# Front_LEDs_v1b.net
KiCad netlist of a schematic drawn in EAGLE
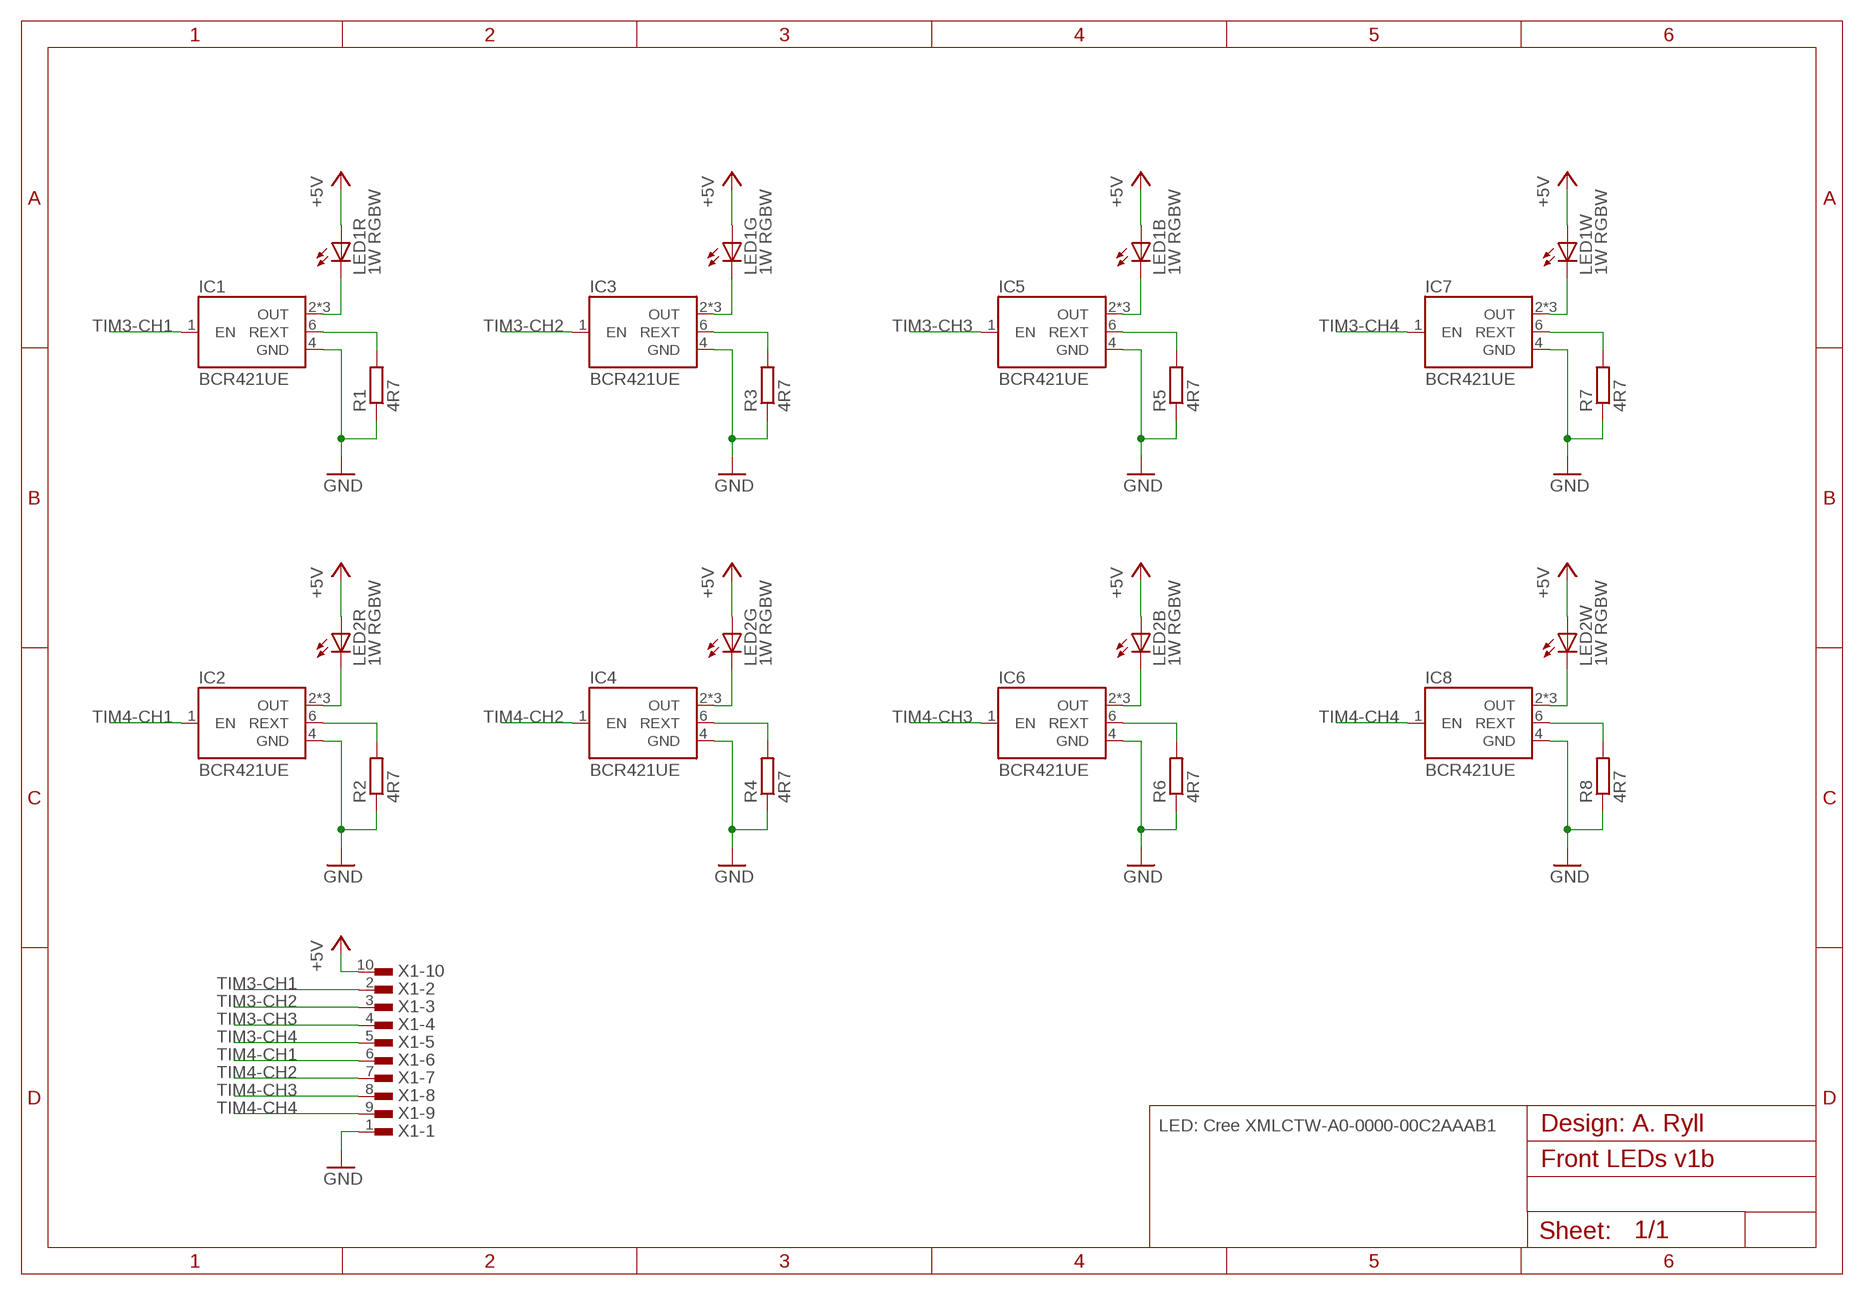
[diagram p0: schematic, sheet 1]

(export (version "E")
  (design (tool "Eeschema 10.0.6"))
  (components
    (comp (ref "IC1")
      (value "BCR421UE")
      (footprint "eagle-import:SOT26")
      (libsource (lib "eagle-import") (part "BCR420_1"))
    )
    (comp (ref "IC2")
      (value "BCR421UE")
      (footprint "eagle-import:SOT26")
      (libsource (lib "eagle-import") (part "BCR420_1"))
    )
    (comp (ref "IC3")
      (value "BCR421UE")
      (footprint "eagle-import:SOT26")
      (libsource (lib "eagle-import") (part "BCR420_1"))
    )
    (comp (ref "IC4")
      (value "BCR421UE")
      (footprint "eagle-import:SOT26")
      (libsource (lib "eagle-import") (part "BCR420_1"))
    )
    (comp (ref "IC5")
      (value "BCR421UE")
      (footprint "eagle-import:SOT26")
      (libsource (lib "eagle-import") (part "BCR420_1"))
    )
    (comp (ref "IC6")
      (value "BCR421UE")
      (footprint "eagle-import:SOT26")
      (libsource (lib "eagle-import") (part "BCR420_1"))
    )
    (comp (ref "IC7")
      (value "BCR421UE")
      (footprint "eagle-import:SOT26")
      (libsource (lib "eagle-import") (part "BCR420_1"))
    )
    (comp (ref "IC8")
      (value "BCR421UE")
      (footprint "eagle-import:SOT26")
      (libsource (lib "eagle-import") (part "BCR420_1"))
    )
    (comp (ref "LED1")
      (value "1W RGBW")
      (footprint "eagle-import:CREE-XLAMP")
      (fields (field (name "PARTNR") "XMLCTW-A0-0000-00C2AAAB1"))
      (libsource (lib "eagle-import") (part "CREE-XLAMP"))
    )
    (comp (ref "LED2")
      (value "1W RGBW")
      (footprint "eagle-import:CREE-XLAMP")
      (fields (field (name "PARTNR") "XMLCTW-A0-0000-00C2AAAB1"))
      (libsource (lib "eagle-import") (part "CREE-XLAMP"))
    )
    (comp (ref "R1")
      (value "4R7")
      (footprint "eagle-import:R0805")
      (libsource (lib "eagle-import") (part "R-EU_R0805"))
    )
    (comp (ref "R2")
      (value "4R7")
      (footprint "eagle-import:R0805")
      (libsource (lib "eagle-import") (part "R-EU_R0805"))
    )
    (comp (ref "R3")
      (value "4R7")
      (footprint "eagle-import:R0805")
      (libsource (lib "eagle-import") (part "R-EU_R0805"))
    )
    (comp (ref "R4")
      (value "4R7")
      (footprint "eagle-import:R0805")
      (libsource (lib "eagle-import") (part "R-EU_R0805"))
    )
    (comp (ref "R5")
      (value "4R7")
      (footprint "eagle-import:R0805")
      (libsource (lib "eagle-import") (part "R-EU_R0805"))
    )
    (comp (ref "R6")
      (value "4R7")
      (footprint "eagle-import:R0805")
      (libsource (lib "eagle-import") (part "R-EU_R0805"))
    )
    (comp (ref "R7")
      (value "4R7")
      (footprint "eagle-import:R0805")
      (libsource (lib "eagle-import") (part "R-EU_R0805"))
    )
    (comp (ref "R8")
      (value "4R7")
      (footprint "eagle-import:R0805")
      (libsource (lib "eagle-import") (part "R-EU_R0805"))
    )
    (comp (ref "X1")
      (value "TE-FPC-1MM-10H")
      (footprint "eagle-import:TE-1-84952-0")
      (libsource (lib "eagle-import") (part "TE-FPC-1MM-10H"))
    )
  )
  (nets
    (net (code "1") (name "+5V") (class "Default")
      (node (ref "LED1") (pin "1") (pinfunction "A_1") (pintype "passive"))
      (node (ref "LED1") (pin "2") (pinfunction "A_2") (pintype "passive"))
      (node (ref "LED1") (pin "3") (pinfunction "A_3") (pintype "passive"))
      (node (ref "LED1") (pin "4") (pinfunction "A_4") (pintype "passive"))
      (node (ref "LED2") (pin "1") (pinfunction "A_1") (pintype "passive"))
      (node (ref "LED2") (pin "2") (pinfunction "A_2") (pintype "passive"))
      (node (ref "LED2") (pin "3") (pinfunction "A_3") (pintype "passive"))
      (node (ref "LED2") (pin "4") (pinfunction "A_4") (pintype "passive"))
      (node (ref "X1") (pin "10") (pinfunction "-1_10") (pintype "bidirectional"))
    )
    (net (code "2") (name "/TIM3-CH1") (class "Default")
      (node (ref "IC1") (pin "1") (pinfunction "EN_1") (pintype "bidirectional"))
      (node (ref "X1") (pin "2") (pinfunction "-1_2") (pintype "bidirectional"))
    )
    (net (code "3") (name "/TIM3-CH2") (class "Default")
      (node (ref "IC3") (pin "1") (pinfunction "EN_1") (pintype "bidirectional"))
      (node (ref "X1") (pin "3") (pinfunction "-1_3") (pintype "bidirectional"))
    )
    (net (code "4") (name "/TIM3-CH3") (class "Default")
      (node (ref "IC5") (pin "1") (pinfunction "EN_1") (pintype "bidirectional"))
      (node (ref "X1") (pin "4") (pinfunction "-1_4") (pintype "bidirectional"))
    )
    (net (code "5") (name "/TIM3-CH4") (class "Default")
      (node (ref "IC7") (pin "1") (pinfunction "EN_1") (pintype "bidirectional"))
      (node (ref "X1") (pin "5") (pinfunction "-1_5") (pintype "bidirectional"))
    )
    (net (code "6") (name "/TIM4-CH1") (class "Default")
      (node (ref "IC2") (pin "1") (pinfunction "EN_1") (pintype "bidirectional"))
      (node (ref "X1") (pin "6") (pinfunction "-1_6") (pintype "bidirectional"))
    )
    (net (code "7") (name "/TIM4-CH2") (class "Default")
      (node (ref "IC4") (pin "1") (pinfunction "EN_1") (pintype "bidirectional"))
      (node (ref "X1") (pin "7") (pinfunction "-1_7") (pintype "bidirectional"))
    )
    (net (code "8") (name "/TIM4-CH3") (class "Default")
      (node (ref "IC6") (pin "1") (pinfunction "EN_1") (pintype "bidirectional"))
      (node (ref "X1") (pin "8") (pinfunction "-1_8") (pintype "bidirectional"))
    )
    (net (code "9") (name "/TIM4-CH4") (class "Default")
      (node (ref "IC8") (pin "1") (pinfunction "EN_1") (pintype "bidirectional"))
      (node (ref "X1") (pin "9") (pinfunction "-1_9") (pintype "bidirectional"))
    )
    (net (code "10") (name "GND") (class "Default")
      (node (ref "IC1") (pin "4") (pinfunction "GND_4") (pintype "bidirectional"))
      (node (ref "IC2") (pin "4") (pinfunction "GND_4") (pintype "bidirectional"))
      (node (ref "IC3") (pin "4") (pinfunction "GND_4") (pintype "bidirectional"))
      (node (ref "IC4") (pin "4") (pinfunction "GND_4") (pintype "bidirectional"))
      (node (ref "IC5") (pin "4") (pinfunction "GND_4") (pintype "bidirectional"))
      (node (ref "IC6") (pin "4") (pinfunction "GND_4") (pintype "bidirectional"))
      (node (ref "IC7") (pin "4") (pinfunction "GND_4") (pintype "bidirectional"))
      (node (ref "IC8") (pin "4") (pinfunction "GND_4") (pintype "bidirectional"))
      (node (ref "R1") (pin "1") (pinfunction "1_1") (pintype "passive"))
      (node (ref "R2") (pin "1") (pinfunction "1_1") (pintype "passive"))
      (node (ref "R3") (pin "1") (pinfunction "1_1") (pintype "passive"))
      (node (ref "R4") (pin "1") (pinfunction "1_1") (pintype "passive"))
      (node (ref "R5") (pin "1") (pinfunction "1_1") (pintype "passive"))
      (node (ref "R6") (pin "1") (pinfunction "1_1") (pintype "passive"))
      (node (ref "R7") (pin "1") (pinfunction "1_1") (pintype "passive"))
      (node (ref "R8") (pin "1") (pinfunction "1_1") (pintype "passive"))
      (node (ref "X1") (pin "1") (pinfunction "-1_1") (pintype "bidirectional"))
    )
    (net (code "11") (name "Net-(IC1-REXT)") (class "Default")
      (node (ref "IC1") (pin "6") (pinfunction "REXT_6") (pintype "bidirectional"))
      (node (ref "R1") (pin "2") (pinfunction "2_2") (pintype "passive"))
    )
    (net (code "12") (name "Net-(IC2-REXT)") (class "Default")
      (node (ref "IC2") (pin "6") (pinfunction "REXT_6") (pintype "bidirectional"))
      (node (ref "R2") (pin "2") (pinfunction "2_2") (pintype "passive"))
    )
    (net (code "13") (name "Net-(IC3-REXT)") (class "Default")
      (node (ref "IC3") (pin "6") (pinfunction "REXT_6") (pintype "bidirectional"))
      (node (ref "R3") (pin "2") (pinfunction "2_2") (pintype "passive"))
    )
    (net (code "14") (name "Net-(IC4-REXT)") (class "Default")
      (node (ref "IC4") (pin "6") (pinfunction "REXT_6") (pintype "bidirectional"))
      (node (ref "R4") (pin "2") (pinfunction "2_2") (pintype "passive"))
    )
    (net (code "15") (name "Net-(IC5-REXT)") (class "Default")
      (node (ref "IC5") (pin "6") (pinfunction "REXT_6") (pintype "bidirectional"))
      (node (ref "R5") (pin "2") (pinfunction "2_2") (pintype "passive"))
    )
    (net (code "16") (name "Net-(IC6-REXT)") (class "Default")
      (node (ref "IC6") (pin "6") (pinfunction "REXT_6") (pintype "bidirectional"))
      (node (ref "R6") (pin "2") (pinfunction "2_2") (pintype "passive"))
    )
    (net (code "17") (name "Net-(IC7-REXT)") (class "Default")
      (node (ref "IC7") (pin "6") (pinfunction "REXT_6") (pintype "bidirectional"))
      (node (ref "R7") (pin "2") (pinfunction "2_2") (pintype "passive"))
    )
    (net (code "18") (name "Net-(IC8-REXT)") (class "Default")
      (node (ref "IC8") (pin "6") (pinfunction "REXT_6") (pintype "bidirectional"))
      (node (ref "R8") (pin "2") (pinfunction "2_2") (pintype "passive"))
    )
    (net (code "19") (name "Net-(LED1A-C)") (class "Default")
      (node (ref "IC5") (pin "2") (pinfunction "OUT_2") (pintype "bidirectional"))
      (node (ref "IC5") (pin "3") (pinfunction "OUT_3") (pintype "bidirectional"))
      (node (ref "IC5") (pin "5") (pinfunction "OUT_5") (pintype "bidirectional"))
      (node (ref "LED1") (pin "6") (pinfunction "C_6") (pintype "passive"))
    )
    (net (code "20") (name "Net-(LED1B-C)") (class "Default")
      (node (ref "IC3") (pin "2") (pinfunction "OUT_2") (pintype "bidirectional"))
      (node (ref "IC3") (pin "3") (pinfunction "OUT_3") (pintype "bidirectional"))
      (node (ref "IC3") (pin "5") (pinfunction "OUT_5") (pintype "bidirectional"))
      (node (ref "LED1") (pin "7") (pinfunction "C_7") (pintype "passive"))
    )
    (net (code "21") (name "Net-(LED1C-C)") (class "Default")
      (node (ref "IC1") (pin "2") (pinfunction "OUT_2") (pintype "bidirectional"))
      (node (ref "IC1") (pin "3") (pinfunction "OUT_3") (pintype "bidirectional"))
      (node (ref "IC1") (pin "5") (pinfunction "OUT_5") (pintype "bidirectional"))
      (node (ref "LED1") (pin "8") (pinfunction "C_8") (pintype "passive"))
    )
    (net (code "22") (name "Net-(LED1D-C)") (class "Default")
      (node (ref "IC7") (pin "2") (pinfunction "OUT_2") (pintype "bidirectional"))
      (node (ref "IC7") (pin "3") (pinfunction "OUT_3") (pintype "bidirectional"))
      (node (ref "IC7") (pin "5") (pinfunction "OUT_5") (pintype "bidirectional"))
      (node (ref "LED1") (pin "5") (pinfunction "C_5") (pintype "passive"))
    )
    (net (code "23") (name "Net-(LED2A-C)") (class "Default")
      (node (ref "IC6") (pin "2") (pinfunction "OUT_2") (pintype "bidirectional"))
      (node (ref "IC6") (pin "3") (pinfunction "OUT_3") (pintype "bidirectional"))
      (node (ref "IC6") (pin "5") (pinfunction "OUT_5") (pintype "bidirectional"))
      (node (ref "LED2") (pin "6") (pinfunction "C_6") (pintype "passive"))
    )
    (net (code "24") (name "Net-(LED2B-C)") (class "Default")
      (node (ref "IC4") (pin "2") (pinfunction "OUT_2") (pintype "bidirectional"))
      (node (ref "IC4") (pin "3") (pinfunction "OUT_3") (pintype "bidirectional"))
      (node (ref "IC4") (pin "5") (pinfunction "OUT_5") (pintype "bidirectional"))
      (node (ref "LED2") (pin "7") (pinfunction "C_7") (pintype "passive"))
    )
    (net (code "25") (name "Net-(LED2C-C)") (class "Default")
      (node (ref "IC2") (pin "2") (pinfunction "OUT_2") (pintype "bidirectional"))
      (node (ref "IC2") (pin "3") (pinfunction "OUT_3") (pintype "bidirectional"))
      (node (ref "IC2") (pin "5") (pinfunction "OUT_5") (pintype "bidirectional"))
      (node (ref "LED2") (pin "8") (pinfunction "C_8") (pintype "passive"))
    )
    (net (code "26") (name "Net-(LED2D-C)") (class "Default")
      (node (ref "IC8") (pin "2") (pinfunction "OUT_2") (pintype "bidirectional"))
      (node (ref "IC8") (pin "3") (pinfunction "OUT_3") (pintype "bidirectional"))
      (node (ref "IC8") (pin "5") (pinfunction "OUT_5") (pintype "bidirectional"))
      (node (ref "LED2") (pin "5") (pinfunction "C_5") (pintype "passive"))
    )
  )
)
